# CAN_Logger.net
KiCad netlist of a schematic drawn in EAGLE
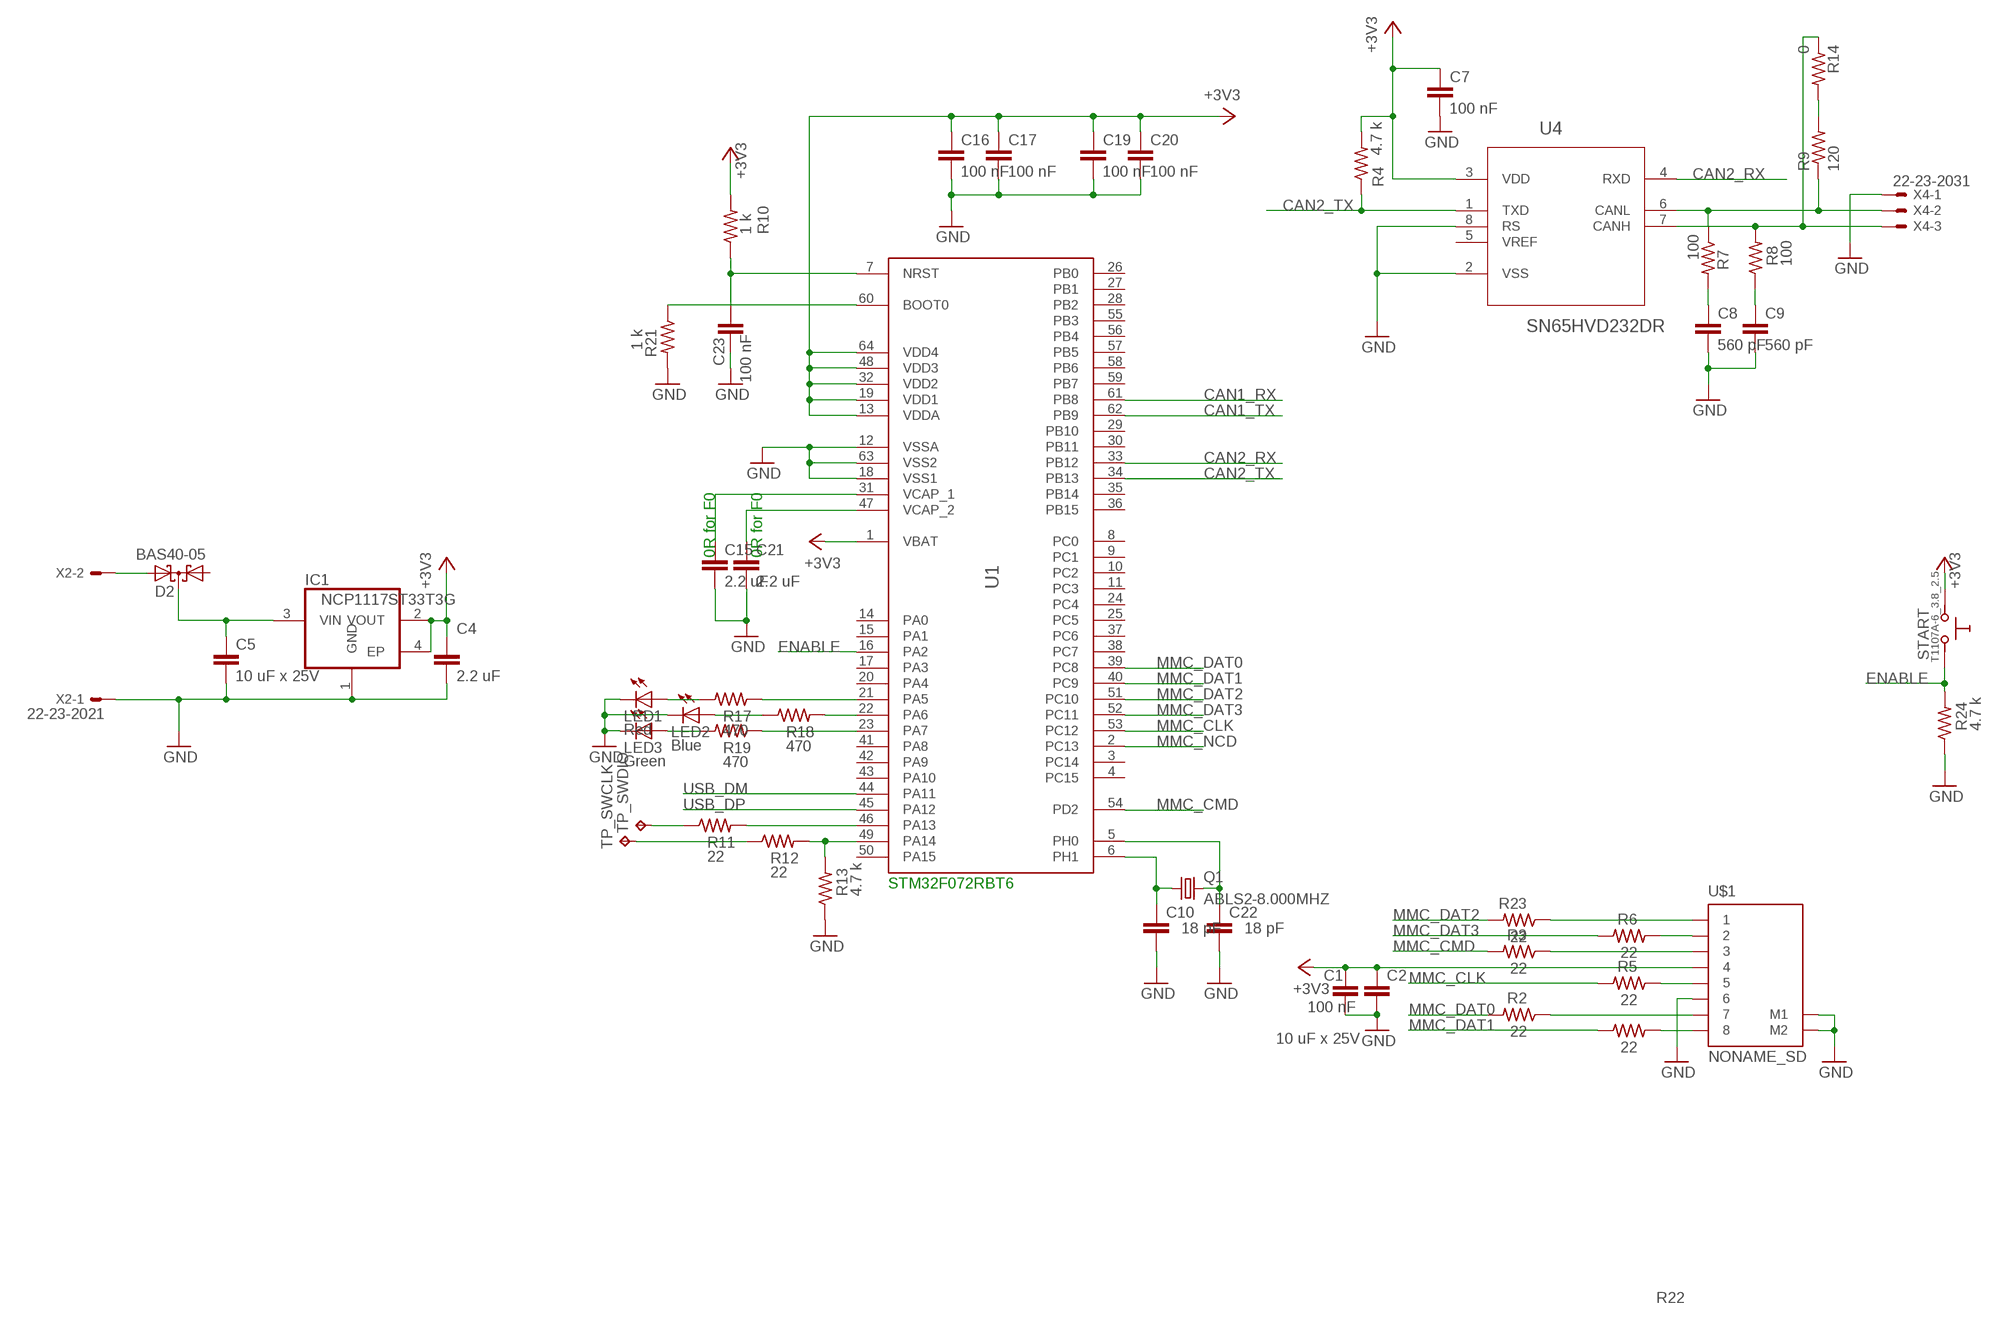
[diagram p0: schematic, sheet 1]

(export (version "E")
  (design (tool "Eeschema 10.0.6"))
  (components
    (comp (ref "C1")
      (value "100 nF")
      (footprint "eagle-import:C0603")
      (libsource (lib "eagle-import") (part "C-EUC0603"))
    )
    (comp (ref "C2")
      (value "10 uF x 25V")
      (footprint "eagle-import:C1206")
      (libsource (lib "eagle-import") (part "C-EUC1206"))
    )
    (comp (ref "C4")
      (value "2.2 uF")
      (footprint "eagle-import:C0603")
      (libsource (lib "eagle-import") (part "C-EUC0603"))
    )
    (comp (ref "C5")
      (value "10 uF x 25V")
      (footprint "eagle-import:C1206")
      (libsource (lib "eagle-import") (part "C-EUC1206"))
    )
    (comp (ref "C7")
      (value "100 nF")
      (footprint "eagle-import:C0603")
      (libsource (lib "eagle-import") (part "C-EUC0603"))
    )
    (comp (ref "C8")
      (value "560 pF")
      (footprint "eagle-import:C0603")
      (libsource (lib "eagle-import") (part "C-EUC0603"))
    )
    (comp (ref "C9")
      (value "560 pF")
      (footprint "eagle-import:C0603")
      (libsource (lib "eagle-import") (part "C-EUC0603"))
    )
    (comp (ref "C10")
      (value "18 pF")
      (footprint "eagle-import:C0603")
      (libsource (lib "eagle-import") (part "C-EUC0603"))
    )
    (comp (ref "C15")
      (value "2.2 uF")
      (footprint "eagle-import:C0603")
      (libsource (lib "eagle-import") (part "C-EUC0603"))
    )
    (comp (ref "C16")
      (value "100 nF")
      (footprint "eagle-import:C0603")
      (libsource (lib "eagle-import") (part "C-EUC0603"))
    )
    (comp (ref "C17")
      (value "100 nF")
      (footprint "eagle-import:C0603")
      (libsource (lib "eagle-import") (part "C-EUC0603"))
    )
    (comp (ref "C19")
      (value "100 nF")
      (footprint "eagle-import:C0603")
      (libsource (lib "eagle-import") (part "C-EUC0603"))
    )
    (comp (ref "C20")
      (value "100 nF")
      (footprint "eagle-import:C0603")
      (libsource (lib "eagle-import") (part "C-EUC0603"))
    )
    (comp (ref "C21")
      (value "2.2 uF")
      (footprint "eagle-import:C0603")
      (libsource (lib "eagle-import") (part "C-EUC0603"))
    )
    (comp (ref "C22")
      (value "18 pF")
      (footprint "eagle-import:C0603")
      (libsource (lib "eagle-import") (part "C-EUC0603"))
    )
    (comp (ref "C23")
      (value "100 nF")
      (footprint "eagle-import:C0603")
      (libsource (lib "eagle-import") (part "C-EUC0603"))
    )
    (comp (ref "D2")
      (value "BAS40-05")
      (footprint "eagle-import:SOT23")
      (libsource (lib "eagle-import") (part "BAS40-05"))
    )
    (comp (ref "IC1")
      (value "NCP1117ST33T3G")
      (footprint "eagle-import:SOT223")
      (fields (field (name "MPN") "REG1117"))
      (libsource (lib "eagle-import") (part "REG1117"))
    )
    (comp (ref "LED1")
      (value "Red")
      (footprint "eagle-import:LED_SML0603")
      (libsource (lib "eagle-import") (part "LED_ESML0603"))
    )
    (comp (ref "LED2")
      (value "Blue")
      (footprint "eagle-import:LED_SML0603")
      (libsource (lib "eagle-import") (part "LED_ESML0603"))
    )
    (comp (ref "LED3")
      (value "Green")
      (footprint "eagle-import:LED_SML0603")
      (libsource (lib "eagle-import") (part "LED_ESML0603"))
    )
    (comp (ref "Q1")
      (value "ABLS2-8.000MHZ")
      (footprint "eagle-import:SM49")
      (libsource (lib "eagle-import") (part "CRYSTALSM49"))
    )
    (comp (ref "R2")
      (value "22")
      (footprint "eagle-import:R0603")
      (libsource (lib "eagle-import") (part "resistor_R-US_R0603"))
    )
    (comp (ref "R3")
      (value "22")
      (footprint "eagle-import:R0603")
      (libsource (lib "eagle-import") (part "resistor_R-US_R0603"))
    )
    (comp (ref "R4")
      (value "4.7 k")
      (footprint "eagle-import:R0603")
      (libsource (lib "eagle-import") (part "resistor_R-US_R0603"))
    )
    (comp (ref "R5")
      (value "22")
      (footprint "eagle-import:R0603")
      (libsource (lib "eagle-import") (part "resistor_R-US_R0603"))
    )
    (comp (ref "R6")
      (value "22")
      (footprint "eagle-import:R0603")
      (libsource (lib "eagle-import") (part "resistor_R-US_R0603"))
    )
    (comp (ref "R7")
      (value "100")
      (footprint "eagle-import:R0603")
      (libsource (lib "eagle-import") (part "resistor_R-US_R0603"))
    )
    (comp (ref "R8")
      (value "100")
      (footprint "eagle-import:R0603")
      (libsource (lib "eagle-import") (part "resistor_R-US_R0603"))
    )
    (comp (ref "R9")
      (value "120")
      (footprint "eagle-import:R0805")
      (libsource (lib "eagle-import") (part "R-US_R0805"))
    )
    (comp (ref "R10")
      (value "1 k")
      (footprint "eagle-import:R0603")
      (libsource (lib "eagle-import") (part "resistor_R-US_R0603"))
    )
    (comp (ref "R11")
      (value "22")
      (footprint "eagle-import:R0603")
      (libsource (lib "eagle-import") (part "resistor_R-US_R0603"))
    )
    (comp (ref "R12")
      (value "22")
      (footprint "eagle-import:R0603")
      (libsource (lib "eagle-import") (part "resistor_R-US_R0603"))
    )
    (comp (ref "R13")
      (value "4.7 k")
      (footprint "eagle-import:R0603")
      (libsource (lib "eagle-import") (part "resistor_R-US_R0603"))
    )
    (comp (ref "R14")
      (value "0")
      (footprint "eagle-import:R0402")
      (libsource (lib "eagle-import") (part "R-US_R0402"))
    )
    (comp (ref "R17")
      (value "470")
      (footprint "eagle-import:R0603")
      (libsource (lib "eagle-import") (part "resistor_R-US_R0603"))
    )
    (comp (ref "R18")
      (value "470")
      (footprint "eagle-import:R0603")
      (libsource (lib "eagle-import") (part "resistor_R-US_R0603"))
    )
    (comp (ref "R19")
      (value "470")
      (footprint "eagle-import:R0603")
      (libsource (lib "eagle-import") (part "resistor_R-US_R0603"))
    )
    (comp (ref "R21")
      (value "1 k")
      (footprint "eagle-import:R0603")
      (libsource (lib "eagle-import") (part "resistor_R-US_R0603"))
    )
    (comp (ref "R22")
      (value "22")
      (footprint "eagle-import:R0603")
      (libsource (lib "eagle-import") (part "resistor_R-US_R0603"))
    )
    (comp (ref "R23")
      (value "22")
      (footprint "eagle-import:R0603")
      (libsource (lib "eagle-import") (part "resistor_R-US_R0603"))
    )
    (comp (ref "R24")
      (value "4.7 k")
      (footprint "eagle-import:R0603")
      (libsource (lib "eagle-import") (part "resistor_R-US_R0603"))
    )
    (comp (ref "START")
      (value "T1107A-6_3.8_2.5")
      (footprint "eagle-import:SW-TAKT_6X3.5_SMD")
      (libsource (lib "eagle-import") (part "SW-TAKT6"))
    )
    (comp (ref "TP_SWCLK")
      (value "TPTP10SQ")
      (footprint "eagle-import:TP10SQ")
      (libsource (lib "eagle-import") (part "TPTP10SQ"))
    )
    (comp (ref "TP_SWDIO")
      (value "TPTP10SQ")
      (footprint "eagle-import:TP10SQ")
      (libsource (lib "eagle-import") (part "TPTP10SQ"))
    )
    (comp (ref "U$1")
      (value "NONAME_SD")
      (footprint "eagle-import:NONAME_SD")
      (libsource (lib "eagle-import") (part "NONAME_SD"))
    )
    (comp (ref "U1")
      (value "STM32F405RGT6")
      (footprint "eagle-import:LQFP64")
      (libsource (lib "eagle-import") (part "STM32F405XXSTM32F405XX"))
    )
    (comp (ref "U4")
      (value "SN65HVD232DR")
      (footprint "eagle-import:SOIC127P600X175-8N")
      (fields (field (name "MPN") "MCP2551-E/SN"))
      (libsource (lib "eagle-import") (part "MCP2551-E/SN"))
    )
    (comp (ref "X2")
      (value "22-23-2021")
      (footprint "eagle-import:22-23-2021")
      (fields (field (name "MF") "MOLEX"))
      (libsource (lib "eagle-import") (part "22-23-2021"))
    )
    (comp (ref "X4")
      (value "22-23-2031")
      (footprint "eagle-import:22-23-2031")
      (fields (field (name "MF") "MOLEX"))
      (libsource (lib "eagle-import") (part "22-23-2031"))
    )
  )
  (nets
    (net (code "1") (name "+3V3") (class "Default")
      (node (ref "C1") (pin "1") (pinfunction "1_1") (pintype "passive"))
      (node (ref "C16") (pin "1") (pinfunction "1_1") (pintype "passive"))
      (node (ref "C17") (pin "1") (pinfunction "1_1") (pintype "passive"))
      (node (ref "C19") (pin "1") (pinfunction "1_1") (pintype "passive"))
      (node (ref "C2") (pin "1") (pinfunction "1_1") (pintype "passive"))
      (node (ref "C20") (pin "1") (pinfunction "1_1") (pintype "passive"))
      (node (ref "C4") (pin "1") (pinfunction "1_1") (pintype "passive"))
      (node (ref "C7") (pin "1") (pinfunction "1_1") (pintype "passive"))
      (node (ref "IC1") (pin "2") (pinfunction "VOUT_2") (pintype "output"))
      (node (ref "IC1") (pin "4") (pinfunction "EP_4") (pintype "output"))
      (node (ref "R10") (pin "2") (pinfunction "2_2") (pintype "passive"))
      (node (ref "R4") (pin "2") (pinfunction "2_2") (pintype "passive"))
      (node (ref "START") (pin "P$1") (pinfunction "0_P$1") (pintype "passive"))
      (node (ref "U$1") (pin "4") (pinfunction "4_4") (pintype "input"))
      (node (ref "U1") (pin "1") (pinfunction "VBAT_1") (pintype "power_in"))
      (node (ref "U1") (pin "13") (pinfunction "VDDA_13") (pintype "power_in"))
      (node (ref "U1") (pin "19") (pinfunction "VDD1_19") (pintype "power_in"))
      (node (ref "U1") (pin "32") (pinfunction "VDD2_32") (pintype "power_in"))
      (node (ref "U1") (pin "48") (pinfunction "VDD3_48") (pintype "power_in"))
      (node (ref "U1") (pin "64") (pinfunction "VDD4_64") (pintype "power_in"))
      (node (ref "U4") (pin "3") (pinfunction "VDD_3") (pintype "power_in"))
    )
    (net (code "2") (name "/CAN1_RX") (class "Default")
      (node (ref "U1") (pin "61") (pinfunction "PB8_61") (pintype "bidirectional"))
    )
    (net (code "3") (name "/CAN1_TX") (class "Default")
      (node (ref "U1") (pin "62") (pinfunction "PB9_62") (pintype "bidirectional"))
    )
    (net (code "4") (name "/CAN2_RX") (class "Default")
      (node (ref "U1") (pin "33") (pinfunction "PB12_33") (pintype "bidirectional"))
      (node (ref "U4") (pin "4") (pinfunction "RXD_4") (pintype "output"))
    )
    (net (code "5") (name "/CAN2_TX") (class "Default")
      (node (ref "R4") (pin "1") (pinfunction "1_1") (pintype "passive"))
      (node (ref "U1") (pin "34") (pinfunction "PB13_34") (pintype "bidirectional"))
      (node (ref "U4") (pin "1") (pinfunction "TXD_1") (pintype "input"))
    )
    (net (code "6") (name "/ENABLE") (class "Default")
      (node (ref "R24") (pin "2") (pinfunction "2_2") (pintype "passive"))
      (node (ref "START") (pin "P$2") (pinfunction "1_P$2") (pintype "passive"))
      (node (ref "U1") (pin "16") (pinfunction "PA2_16") (pintype "bidirectional"))
    )
    (net (code "7") (name "/MMC_CLK") (class "Default")
      (node (ref "R5") (pin "2") (pinfunction "2_2") (pintype "passive"))
      (node (ref "U1") (pin "53") (pinfunction "PC12_53") (pintype "bidirectional"))
    )
    (net (code "8") (name "/MMC_CMD") (class "Default")
      (node (ref "R3") (pin "2") (pinfunction "2_2") (pintype "passive"))
      (node (ref "U1") (pin "54") (pinfunction "PD2_54") (pintype "bidirectional"))
    )
    (net (code "9") (name "/MMC_DAT0") (class "Default")
      (node (ref "R2") (pin "2") (pinfunction "2_2") (pintype "passive"))
      (node (ref "U1") (pin "39") (pinfunction "PC8_39") (pintype "bidirectional"))
    )
    (net (code "10") (name "/MMC_DAT1") (class "Default")
      (node (ref "R22") (pin "2") (pinfunction "2_2") (pintype "passive"))
      (node (ref "U1") (pin "40") (pinfunction "PC9_40") (pintype "bidirectional"))
    )
    (net (code "11") (name "/MMC_DAT2") (class "Default")
      (node (ref "R23") (pin "2") (pinfunction "2_2") (pintype "passive"))
      (node (ref "U1") (pin "51") (pinfunction "PC10_51") (pintype "bidirectional"))
    )
    (net (code "12") (name "/MMC_DAT3") (class "Default")
      (node (ref "R6") (pin "2") (pinfunction "2_2") (pintype "passive"))
      (node (ref "U1") (pin "52") (pinfunction "PC11_52") (pintype "bidirectional"))
    )
    (net (code "13") (name "/MMC_NCD") (class "Default")
      (node (ref "U1") (pin "2") (pinfunction "PC13_2") (pintype "bidirectional"))
    )
    (net (code "14") (name "/USB_DM") (class "Default")
      (node (ref "U1") (pin "44") (pinfunction "PA11_44") (pintype "bidirectional"))
    )
    (net (code "15") (name "/USB_DP") (class "Default")
      (node (ref "U1") (pin "45") (pinfunction "PA12_45") (pintype "bidirectional"))
    )
    (net (code "16") (name "GND") (class "Default")
      (node (ref "C1") (pin "2") (pinfunction "2_2") (pintype "passive"))
      (node (ref "C10") (pin "2") (pinfunction "2_2") (pintype "passive"))
      (node (ref "C15") (pin "2") (pinfunction "2_2") (pintype "passive"))
      (node (ref "C16") (pin "2") (pinfunction "2_2") (pintype "passive"))
      (node (ref "C17") (pin "2") (pinfunction "2_2") (pintype "passive"))
      (node (ref "C19") (pin "2") (pinfunction "2_2") (pintype "passive"))
      (node (ref "C2") (pin "2") (pinfunction "2_2") (pintype "passive"))
      (node (ref "C20") (pin "2") (pinfunction "2_2") (pintype "passive"))
      (node (ref "C21") (pin "2") (pinfunction "2_2") (pintype "passive"))
      (node (ref "C22") (pin "2") (pinfunction "2_2") (pintype "passive"))
      (node (ref "C23") (pin "2") (pinfunction "2_2") (pintype "passive"))
      (node (ref "C4") (pin "2") (pinfunction "2_2") (pintype "passive"))
      (node (ref "C5") (pin "2") (pinfunction "2_2") (pintype "passive"))
      (node (ref "C7") (pin "2") (pinfunction "2_2") (pintype "passive"))
      (node (ref "C8") (pin "2") (pinfunction "2_2") (pintype "passive"))
      (node (ref "C9") (pin "2") (pinfunction "2_2") (pintype "passive"))
      (node (ref "IC1") (pin "1") (pinfunction "GND_1") (pintype "power_in"))
      (node (ref "LED1") (pin "C") (pinfunction "C_C") (pintype "passive"))
      (node (ref "LED2") (pin "C") (pinfunction "C_C") (pintype "passive"))
      (node (ref "LED3") (pin "C") (pinfunction "C_C") (pintype "passive"))
      (node (ref "R13") (pin "1") (pinfunction "1_1") (pintype "passive"))
      (node (ref "R21") (pin "2") (pinfunction "2_2") (pintype "passive"))
      (node (ref "R24") (pin "1") (pinfunction "1_1") (pintype "passive"))
      (node (ref "U$1") (pin "6") (pinfunction "6_6") (pintype "input"))
      (node (ref "U$1") (pin "M1") (pinfunction "M1_M1") (pintype "input"))
      (node (ref "U$1") (pin "M2") (pinfunction "M2_M2") (pintype "input"))
      (node (ref "U1") (pin "12") (pinfunction "VSSA_12") (pintype "power_in"))
      (node (ref "U1") (pin "18") (pinfunction "VSS1_18") (pintype "power_in"))
      (node (ref "U1") (pin "63") (pinfunction "VSS2_63") (pintype "power_in"))
      (node (ref "U4") (pin "2") (pinfunction "VSS_2") (pintype "power_in"))
      (node (ref "U4") (pin "8") (pinfunction "RS_8") (pintype "input"))
      (node (ref "X2") (pin "1") (pinfunction "S_1") (pintype "passive"))
      (node (ref "X4") (pin "1") (pinfunction "S_1") (pintype "passive"))
    )
    (net (code "17") (name "Net-(C8-Pad1)") (class "Default")
      (node (ref "C8") (pin "1") (pinfunction "1_1") (pintype "passive"))
      (node (ref "R7") (pin "2") (pinfunction "2_2") (pintype "passive"))
    )
    (net (code "18") (name "Net-(C9-Pad1)") (class "Default")
      (node (ref "C9") (pin "1") (pinfunction "1_1") (pintype "passive"))
      (node (ref "R8") (pin "1") (pinfunction "1_1") (pintype "passive"))
    )
    (net (code "19") (name "Net-(D2-A2)") (class "Default")
      (node (ref "D2") (pin "2") (pinfunction "A2_2") (pintype "passive"))
      (node (ref "X2") (pin "2") (pinfunction "S_2") (pintype "passive"))
    )
    (net (code "20") (name "Net-(D2-C)") (class "Default")
      (node (ref "C5") (pin "1") (pinfunction "1_1") (pintype "passive"))
      (node (ref "D2") (pin "3") (pinfunction "C_3") (pintype "passive"))
      (node (ref "IC1") (pin "3") (pinfunction "VIN_3") (pintype "input"))
    )
    (net (code "21") (name "Net-(LED1-PadA)") (class "Default")
      (node (ref "LED1") (pin "A") (pinfunction "A_A") (pintype "passive"))
      (node (ref "R17") (pin "1") (pinfunction "1_1") (pintype "passive"))
    )
    (net (code "22") (name "Net-(LED2-PadA)") (class "Default")
      (node (ref "LED2") (pin "A") (pinfunction "A_A") (pintype "passive"))
      (node (ref "R18") (pin "1") (pinfunction "1_1") (pintype "passive"))
    )
    (net (code "23") (name "Net-(LED3-PadA)") (class "Default")
      (node (ref "LED3") (pin "A") (pinfunction "A_A") (pintype "passive"))
      (node (ref "R19") (pin "1") (pinfunction "1_1") (pintype "passive"))
    )
    (net (code "24") (name "Net-(R2-Pad1)") (class "Default")
      (node (ref "R2") (pin "1") (pinfunction "1_1") (pintype "passive"))
      (node (ref "U$1") (pin "7") (pinfunction "7_7") (pintype "input"))
    )
    (net (code "25") (name "Net-(R3-Pad1)") (class "Default")
      (node (ref "R3") (pin "1") (pinfunction "1_1") (pintype "passive"))
      (node (ref "U$1") (pin "3") (pinfunction "3_3") (pintype "input"))
    )
    (net (code "26") (name "Net-(R5-Pad1)") (class "Default")
      (node (ref "R5") (pin "1") (pinfunction "1_1") (pintype "passive"))
      (node (ref "U$1") (pin "5") (pinfunction "5_5") (pintype "input"))
    )
    (net (code "27") (name "Net-(R6-Pad1)") (class "Default")
      (node (ref "R6") (pin "1") (pinfunction "1_1") (pintype "passive"))
      (node (ref "U$1") (pin "2") (pinfunction "2_2") (pintype "input"))
    )
    (net (code "28") (name "Net-(R11-Pad1)") (class "Default")
      (node (ref "R11") (pin "1") (pinfunction "1_1") (pintype "passive"))
      (node (ref "TP_SWDIO") (pin "TP") (pinfunction "TP_TP") (pintype "input"))
    )
    (net (code "29") (name "Net-(R12-Pad1)") (class "Default")
      (node (ref "R12") (pin "1") (pinfunction "1_1") (pintype "passive"))
      (node (ref "TP_SWCLK") (pin "TP") (pinfunction "TP_TP") (pintype "input"))
    )
    (net (code "30") (name "Net-(R14-Pad2)") (class "Default")
      (node (ref "R14") (pin "2") (pinfunction "2_2") (pintype "passive"))
      (node (ref "R9") (pin "2") (pinfunction "2_2") (pintype "passive"))
    )
    (net (code "31") (name "Net-(R22-Pad1)") (class "Default")
      (node (ref "R22") (pin "1") (pinfunction "1_1") (pintype "passive"))
      (node (ref "U$1") (pin "8") (pinfunction "8_8") (pintype "input"))
    )
    (net (code "32") (name "Net-(R23-Pad1)") (class "Default")
      (node (ref "R23") (pin "1") (pinfunction "1_1") (pintype "passive"))
      (node (ref "U$1") (pin "1") (pinfunction "1_1") (pintype "input"))
    )
    (net (code "33") (name "Net-(U1-BOOT0)") (class "Default")
      (node (ref "R21") (pin "1") (pinfunction "1_1") (pintype "passive"))
      (node (ref "U1") (pin "60") (pinfunction "BOOT0_60") (pintype "bidirectional"))
    )
    (net (code "34") (name "Net-(U1-NRST)") (class "Default")
      (node (ref "C23") (pin "1") (pinfunction "1_1") (pintype "passive"))
      (node (ref "R10") (pin "1") (pinfunction "1_1") (pintype "passive"))
      (node (ref "U1") (pin "7") (pinfunction "NRST_7") (pintype "bidirectional"))
    )
    (net (code "35") (name "Net-(U1-PA5)") (class "Default")
      (node (ref "R17") (pin "2") (pinfunction "2_2") (pintype "passive"))
      (node (ref "U1") (pin "21") (pinfunction "PA5_21") (pintype "bidirectional"))
    )
    (net (code "36") (name "Net-(U1-PA6)") (class "Default")
      (node (ref "R18") (pin "2") (pinfunction "2_2") (pintype "passive"))
      (node (ref "U1") (pin "22") (pinfunction "PA6_22") (pintype "bidirectional"))
    )
    (net (code "37") (name "Net-(U1-PA7)") (class "Default")
      (node (ref "R19") (pin "2") (pinfunction "2_2") (pintype "passive"))
      (node (ref "U1") (pin "23") (pinfunction "PA7_23") (pintype "bidirectional"))
    )
    (net (code "38") (name "Net-(U1-PA13)") (class "Default")
      (node (ref "R11") (pin "2") (pinfunction "2_2") (pintype "passive"))
      (node (ref "U1") (pin "46") (pinfunction "PA13_46") (pintype "bidirectional"))
    )
    (net (code "39") (name "Net-(U1-PA14)") (class "Default")
      (node (ref "R12") (pin "2") (pinfunction "2_2") (pintype "passive"))
      (node (ref "R13") (pin "2") (pinfunction "2_2") (pintype "passive"))
      (node (ref "U1") (pin "49") (pinfunction "PA14_49") (pintype "bidirectional"))
    )
    (net (code "40") (name "Net-(U1-PH0)") (class "Default")
      (node (ref "C22") (pin "1") (pinfunction "1_1") (pintype "passive"))
      (node (ref "Q1") (pin "2") (pinfunction "2_2") (pintype "passive"))
      (node (ref "U1") (pin "5") (pinfunction "PH0_5") (pintype "bidirectional"))
    )
    (net (code "41") (name "Net-(U1-PH1)") (class "Default")
      (node (ref "C10") (pin "1") (pinfunction "1_1") (pintype "passive"))
      (node (ref "Q1") (pin "1") (pinfunction "1_1") (pintype "passive"))
      (node (ref "U1") (pin "6") (pinfunction "PH1_6") (pintype "bidirectional"))
    )
    (net (code "42") (name "Net-(U1-VCAP_1)") (class "Default")
      (node (ref "C15") (pin "1") (pinfunction "1_1") (pintype "passive"))
      (node (ref "U1") (pin "31") (pinfunction "VCAP_1_31") (pintype "power_in"))
    )
    (net (code "43") (name "Net-(U1-VCAP_2)") (class "Default")
      (node (ref "C21") (pin "1") (pinfunction "1_1") (pintype "passive"))
      (node (ref "U1") (pin "47") (pinfunction "VCAP_2_47") (pintype "power_in"))
    )
    (net (code "44") (name "Net-(U4-CANH)") (class "Default")
      (node (ref "R14") (pin "1") (pinfunction "1_1") (pintype "passive"))
      (node (ref "R8") (pin "2") (pinfunction "2_2") (pintype "passive"))
      (node (ref "U4") (pin "7") (pinfunction "CANH_7") (pintype "output"))
      (node (ref "X4") (pin "3") (pinfunction "S_3") (pintype "passive"))
    )
    (net (code "45") (name "Net-(U4-CANL)") (class "Default")
      (node (ref "R7") (pin "1") (pinfunction "1_1") (pintype "passive"))
      (node (ref "R9") (pin "1") (pinfunction "1_1") (pintype "passive"))
      (node (ref "U4") (pin "6") (pinfunction "CANL_6") (pintype "output"))
      (node (ref "X4") (pin "2") (pinfunction "S_2") (pintype "passive"))
    )
    (net (code "46") (name "unconnected-(D2-A1-Pad1)") (class "Default")
      (node (ref "D2") (pin "1") (pinfunction "A1_1") (pintype "passive"))
    )
    (net (code "47") (name "unconnected-(U1-PA0-Pad14)") (class "Default")
      (node (ref "U1") (pin "14") (pinfunction "PA0_14") (pintype "bidirectional"))
    )
    (net (code "48") (name "unconnected-(U1-PA1-Pad15)") (class "Default")
      (node (ref "U1") (pin "15") (pinfunction "PA1_15") (pintype "bidirectional"))
    )
    (net (code "49") (name "unconnected-(U1-PA3-Pad17)") (class "Default")
      (node (ref "U1") (pin "17") (pinfunction "PA3_17") (pintype "bidirectional"))
    )
    (net (code "50") (name "unconnected-(U1-PA4-Pad20)") (class "Default")
      (node (ref "U1") (pin "20") (pinfunction "PA4_20") (pintype "bidirectional"))
    )
    (net (code "51") (name "unconnected-(U1-PA8-Pad41)") (class "Default")
      (node (ref "U1") (pin "41") (pinfunction "PA8_41") (pintype "bidirectional"))
    )
    (net (code "52") (name "unconnected-(U1-PA9-Pad42)") (class "Default")
      (node (ref "U1") (pin "42") (pinfunction "PA9_42") (pintype "bidirectional"))
    )
    (net (code "53") (name "unconnected-(U1-PA10-Pad43)") (class "Default")
      (node (ref "U1") (pin "43") (pinfunction "PA10_43") (pintype "bidirectional"))
    )
    (net (code "54") (name "unconnected-(U1-PA15-Pad50)") (class "Default")
      (node (ref "U1") (pin "50") (pinfunction "PA15_50") (pintype "bidirectional"))
    )
    (net (code "55") (name "unconnected-(U1-PB0-Pad26)") (class "Default")
      (node (ref "U1") (pin "26") (pinfunction "PB0_26") (pintype "bidirectional"))
    )
    (net (code "56") (name "unconnected-(U1-PB1-Pad27)") (class "Default")
      (node (ref "U1") (pin "27") (pinfunction "PB1_27") (pintype "bidirectional"))
    )
    (net (code "57") (name "unconnected-(U1-PB2-Pad28)") (class "Default")
      (node (ref "U1") (pin "28") (pinfunction "PB2_28") (pintype "bidirectional"))
    )
    (net (code "58") (name "unconnected-(U1-PB3-Pad55)") (class "Default")
      (node (ref "U1") (pin "55") (pinfunction "PB3_55") (pintype "bidirectional"))
    )
    (net (code "59") (name "unconnected-(U1-PB4-Pad56)") (class "Default")
      (node (ref "U1") (pin "56") (pinfunction "PB4_56") (pintype "bidirectional"))
    )
    (net (code "60") (name "unconnected-(U1-PB5-Pad57)") (class "Default")
      (node (ref "U1") (pin "57") (pinfunction "PB5_57") (pintype "bidirectional"))
    )
    (net (code "61") (name "unconnected-(U1-PB6-Pad58)") (class "Default")
      (node (ref "U1") (pin "58") (pinfunction "PB6_58") (pintype "bidirectional"))
    )
    (net (code "62") (name "unconnected-(U1-PB7-Pad59)") (class "Default")
      (node (ref "U1") (pin "59") (pinfunction "PB7_59") (pintype "bidirectional"))
    )
    (net (code "63") (name "unconnected-(U1-PB10-Pad29)") (class "Default")
      (node (ref "U1") (pin "29") (pinfunction "PB10_29") (pintype "bidirectional"))
    )
    (net (code "64") (name "unconnected-(U1-PB11-Pad30)") (class "Default")
      (node (ref "U1") (pin "30") (pinfunction "PB11_30") (pintype "bidirectional"))
    )
    (net (code "65") (name "unconnected-(U1-PB14-Pad35)") (class "Default")
      (node (ref "U1") (pin "35") (pinfunction "PB14_35") (pintype "bidirectional"))
    )
    (net (code "66") (name "unconnected-(U1-PB15-Pad36)") (class "Default")
      (node (ref "U1") (pin "36") (pinfunction "PB15_36") (pintype "bidirectional"))
    )
    (net (code "67") (name "unconnected-(U1-PC0-Pad8)") (class "Default")
      (node (ref "U1") (pin "8") (pinfunction "PC0_8") (pintype "bidirectional"))
    )
    (net (code "68") (name "unconnected-(U1-PC1-Pad9)") (class "Default")
      (node (ref "U1") (pin "9") (pinfunction "PC1_9") (pintype "bidirectional"))
    )
    (net (code "69") (name "unconnected-(U1-PC2-Pad10)") (class "Default")
      (node (ref "U1") (pin "10") (pinfunction "PC2_10") (pintype "bidirectional"))
    )
    (net (code "70") (name "unconnected-(U1-PC3-Pad11)") (class "Default")
      (node (ref "U1") (pin "11") (pinfunction "PC3_11") (pintype "bidirectional"))
    )
    (net (code "71") (name "unconnected-(U1-PC4-Pad24)") (class "Default")
      (node (ref "U1") (pin "24") (pinfunction "PC4_24") (pintype "bidirectional"))
    )
    (net (code "72") (name "unconnected-(U1-PC5-Pad25)") (class "Default")
      (node (ref "U1") (pin "25") (pinfunction "PC5_25") (pintype "bidirectional"))
    )
    (net (code "73") (name "unconnected-(U1-PC6-Pad37)") (class "Default")
      (node (ref "U1") (pin "37") (pinfunction "PC6_37") (pintype "bidirectional"))
    )
    (net (code "74") (name "unconnected-(U1-PC7-Pad38)") (class "Default")
      (node (ref "U1") (pin "38") (pinfunction "PC7_38") (pintype "bidirectional"))
    )
    (net (code "75") (name "unconnected-(U1-PC14-Pad3)") (class "Default")
      (node (ref "U1") (pin "3") (pinfunction "PC14_3") (pintype "bidirectional"))
    )
    (net (code "76") (name "unconnected-(U1-PC15-Pad4)") (class "Default")
      (node (ref "U1") (pin "4") (pinfunction "PC15_4") (pintype "bidirectional"))
    )
    (net (code "77") (name "unconnected-(U4-VREF-Pad5)") (class "Default")
      (node (ref "U4") (pin "5") (pinfunction "VREF_5") (pintype "input"))
    )
  )
)
